# ai_avr_synth.net
KiCad netlist of a schematic drawn in EAGLE
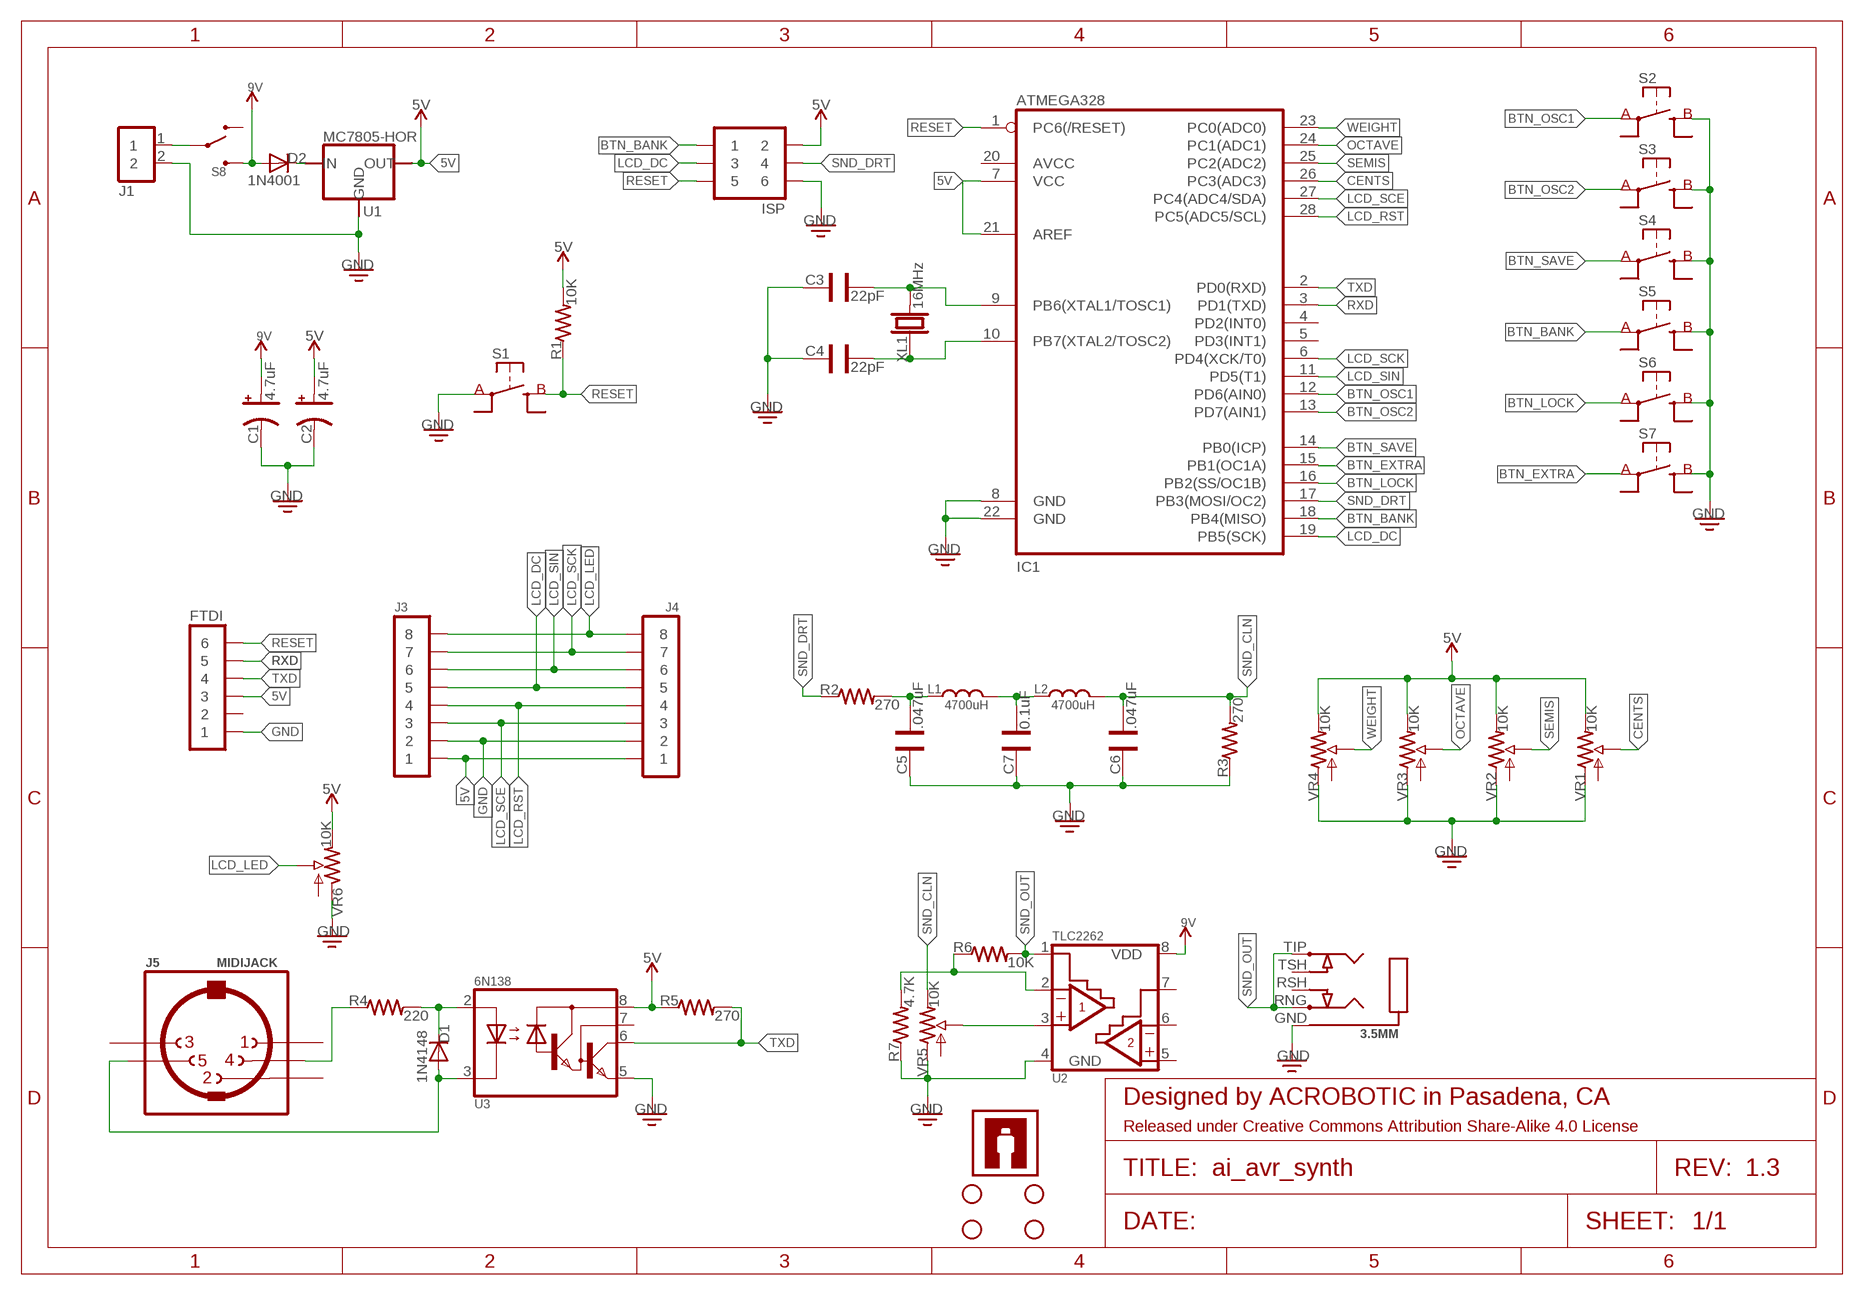
[diagram p0: schematic, sheet 1]

(export (version "E")
  (design (tool "Eeschema 10.0.6"))
  (components
    (comp (ref "3.5MM")
      (value "STEREOJACKSJ1-351XNG")
      (footprint "eagle-import:SJ1-351XNG")
      (libsource (lib "eagle-import") (part "STEREOJACKSJ1-351XNG"))
    )
    (comp (ref "C1")
      (value "4.7uF")
      (footprint "eagle-import:CAP-POL-025X50")
      (libsource (lib "eagle-import") (part "CAP-POL025X50"))
    )
    (comp (ref "C2")
      (value "4.7uF")
      (footprint "eagle-import:CAP-POL-025X50")
      (libsource (lib "eagle-import") (part "CAP-POL025X50"))
    )
    (comp (ref "C3")
      (value "22pF")
      (footprint "eagle-import:CAP-025X050")
      (libsource (lib "eagle-import") (part "CAP025X050"))
    )
    (comp (ref "C4")
      (value "22pF")
      (footprint "eagle-import:CAP-025X050")
      (libsource (lib "eagle-import") (part "CAP025X050"))
    )
    (comp (ref "C5")
      (value ".047uF")
      (footprint "eagle-import:CAP-025X050")
      (libsource (lib "eagle-import") (part "CAP025X050"))
    )
    (comp (ref "C6")
      (value ".047uF")
      (footprint "eagle-import:CAP-025X050")
      (libsource (lib "eagle-import") (part "CAP025X050"))
    )
    (comp (ref "C7")
      (value "0.1uF")
      (footprint "eagle-import:CAP-025X050")
      (libsource (lib "eagle-import") (part "CAP025X050"))
    )
    (comp (ref "D1")
      (value "1N4148")
      (footprint "eagle-import:TH-1N914")
      (libsource (lib "eagle-import") (part "DIODETH-1N914"))
    )
    (comp (ref "D2")
      (value "1N4001")
      (footprint "eagle-import:TH-1N914")
      (libsource (lib "eagle-import") (part "DIODETH-1N914"))
    )
    (comp (ref "FRAME1")
      (value "FRAME-LETTER")
      (footprint "eagle-import:CREATIVE-COMMONS")
      (fields (field (name "REV") "1.3"))
      (libsource (lib "eagle-import") (part "FRAME-LETTER"))
    )
    (comp (ref "FTDI")
      (value "1X06")
      (footprint "eagle-import:1X06")
      (libsource (lib "eagle-import") (part "1X06"))
    )
    (comp (ref "IC1")
      (value "ATMEGA328P-PDIP")
      (footprint "eagle-import:DIL28")
      (libsource (lib "eagle-import") (part "ATMEGA328P-PDIP"))
    )
    (comp (ref "ISP")
      (value "2X03")
      (footprint "eagle-import:2X03")
      (libsource (lib "eagle-import") (part "2X03"))
    )
    (comp (ref "J1")
      (value "1X02ST")
      (footprint "eagle-import:1X02-ST")
      (libsource (lib "eagle-import") (part "1X02ST"))
    )
    (comp (ref "J3")
      (value "1X08")
      (footprint "eagle-import:1X08")
      (libsource (lib "eagle-import") (part "1X08"))
    )
    (comp (ref "J4")
      (value "1X08")
      (footprint "eagle-import:1X08")
      (libsource (lib "eagle-import") (part "1X08"))
    )
    (comp (ref "J5")
      (value "MIDIJACK")
      (footprint "eagle-import:CP-2350")
      (libsource (lib "eagle-import") (part "MIDIJACK"))
    )
    (comp (ref "L1")
      (value "4700uH")
      (footprint "eagle-import:RLB0912")
      (libsource (lib "eagle-import") (part "INDRLB0912"))
    )
    (comp (ref "L2")
      (value "4700uH")
      (footprint "eagle-import:RLB0912")
      (libsource (lib "eagle-import") (part "INDRLB0912"))
    )
    (comp (ref "R1")
      (value "10K")
      (footprint "eagle-import:RES-AXIAL-0.4")
      (libsource (lib "eagle-import") (part "RESAXIAL-0.4"))
    )
    (comp (ref "R2")
      (value "270")
      (footprint "eagle-import:RES-AXIAL-0.4")
      (libsource (lib "eagle-import") (part "RESAXIAL-0.4"))
    )
    (comp (ref "R3")
      (value "270")
      (footprint "eagle-import:RES-AXIAL-0.4")
      (libsource (lib "eagle-import") (part "RESAXIAL-0.4"))
    )
    (comp (ref "R4")
      (value "220")
      (footprint "eagle-import:RES-AXIAL-0.4")
      (libsource (lib "eagle-import") (part "RESAXIAL-0.4"))
    )
    (comp (ref "R5")
      (value "270")
      (footprint "eagle-import:RES-AXIAL-0.4")
      (libsource (lib "eagle-import") (part "RESAXIAL-0.4"))
    )
    (comp (ref "R6")
      (value "10K")
      (footprint "eagle-import:RES-AXIAL-0.4")
      (libsource (lib "eagle-import") (part "RESAXIAL-0.4"))
    )
    (comp (ref "R7")
      (value "4.7K")
      (footprint "eagle-import:RES-AXIAL-0.4")
      (libsource (lib "eagle-import") (part "RESAXIAL-0.4"))
    )
    (comp (ref "S1")
      (value "SW-SPSTTH06X06")
      (footprint "eagle-import:SW-SPST-TH06X06")
      (libsource (lib "eagle-import") (part "SW-SPSTTH06X06"))
    )
    (comp (ref "S2")
      (value "SW-SPSTTH06X06")
      (footprint "eagle-import:SW-SPST-TH06X06")
      (libsource (lib "eagle-import") (part "SW-SPSTTH06X06"))
    )
    (comp (ref "S3")
      (value "SW-SPSTTH06X06")
      (footprint "eagle-import:SW-SPST-TH06X06")
      (libsource (lib "eagle-import") (part "SW-SPSTTH06X06"))
    )
    (comp (ref "S4")
      (value "SW-SPSTTH06X06")
      (footprint "eagle-import:SW-SPST-TH06X06")
      (libsource (lib "eagle-import") (part "SW-SPSTTH06X06"))
    )
    (comp (ref "S5")
      (value "SW-SPSTTH06X06")
      (footprint "eagle-import:SW-SPST-TH06X06")
      (libsource (lib "eagle-import") (part "SW-SPSTTH06X06"))
    )
    (comp (ref "S6")
      (value "SW-SPSTTH06X06")
      (footprint "eagle-import:SW-SPST-TH06X06")
      (libsource (lib "eagle-import") (part "SW-SPSTTH06X06"))
    )
    (comp (ref "S7")
      (value "SW-SPSTTH06X06")
      (footprint "eagle-import:SW-SPST-TH06X06")
      (libsource (lib "eagle-import") (part "SW-SPSTTH06X06"))
    )
    (comp (ref "S8")
      (value "SW-SPDTTH")
      (footprint "eagle-import:SW-SPDT-TH")
      (libsource (lib "eagle-import") (part "SW-SPDTTH"))
    )
    (comp (ref "STANDOFF5")
      (value "STAND-OFF4")
      (footprint "eagle-import:STAND-OFF-4")
      (libsource (lib "eagle-import") (part "STAND-OFF4"))
    )
    (comp (ref "STANDOFF6")
      (value "STAND-OFF4")
      (footprint "eagle-import:STAND-OFF-4")
      (libsource (lib "eagle-import") (part "STAND-OFF4"))
    )
    (comp (ref "STANDOFF7")
      (value "STAND-OFF4")
      (footprint "eagle-import:STAND-OFF-4")
      (libsource (lib "eagle-import") (part "STAND-OFF4"))
    )
    (comp (ref "STANDOFF8")
      (value "STAND-OFF4")
      (footprint "eagle-import:STAND-OFF-4")
      (libsource (lib "eagle-import") (part "STAND-OFF4"))
    )
    (comp (ref "U$5")
      (value "AI-LOGOXS")
      (footprint "eagle-import:AI-LOGO-XS")
      (libsource (lib "eagle-import") (part "AI-LOGOXS"))
    )
    (comp (ref "U1")
      (value "MC7805-HOR")
      (footprint "eagle-import:TO220")
      (libsource (lib "eagle-import") (part "MC7805-HOR"))
    )
    (comp (ref "U2")
      (value "TLC2262")
      (footprint "eagle-import:DIL08")
      (libsource (lib "eagle-import") (part "TLC2262"))
    )
    (comp (ref "U3")
      (value "6N138")
      (footprint "eagle-import:DIL08")
      (libsource (lib "eagle-import") (part "6N138"))
    )
    (comp (ref "VR1")
      (value "10K")
      (footprint "eagle-import:POT-09X09")
      (libsource (lib "eagle-import") (part "POT09X09"))
    )
    (comp (ref "VR2")
      (value "10K")
      (footprint "eagle-import:POT-09X09")
      (libsource (lib "eagle-import") (part "POT09X09"))
    )
    (comp (ref "VR3")
      (value "10K")
      (footprint "eagle-import:POT-09X09")
      (libsource (lib "eagle-import") (part "POT09X09"))
    )
    (comp (ref "VR4")
      (value "10K")
      (footprint "eagle-import:POT-09X09")
      (libsource (lib "eagle-import") (part "POT09X09"))
    )
    (comp (ref "VR5")
      (value "10K")
      (footprint "eagle-import:POT-09X09")
      (libsource (lib "eagle-import") (part "POT09X09"))
    )
    (comp (ref "VR6")
      (value "10K")
      (footprint "eagle-import:POT-05X05")
      (libsource (lib "eagle-import") (part "POT05X05"))
    )
    (comp (ref "XL1")
      (value "16MHz")
      (footprint "eagle-import:HC49S")
      (libsource (lib "eagle-import") (part "CRYSTALHC49S"))
    )
  )
  (nets
    (net (code "1") (name "5V") (class "Default")
      (node (ref "C2") (pin "A") (pinfunction "A_A") (pintype "passive"))
      (node (ref "FTDI") (pin "3") (pinfunction "3_3") (pintype "bidirectional"))
      (node (ref "IC1") (pin "21") (pinfunction "AREF_21") (pintype "bidirectional"))
      (node (ref "IC1") (pin "7") (pinfunction "VCC_7") (pintype "bidirectional"))
      (node (ref "ISP") (pin "2") (pinfunction "2_2") (pintype "bidirectional"))
      (node (ref "J3") (pin "1") (pinfunction "1_1") (pintype "bidirectional"))
      (node (ref "J4") (pin "1") (pinfunction "1_1") (pintype "bidirectional"))
      (node (ref "R1") (pin "P$2") (pinfunction "2_P$2") (pintype "passive"))
      (node (ref "R5") (pin "P$1") (pinfunction "1_P$1") (pintype "passive"))
      (node (ref "U1") (pin "OUT") (pinfunction "OUT_OUT") (pintype "power_in"))
      (node (ref "U3") (pin "8") (pinfunction "VCC_8") (pintype "passive"))
      (node (ref "VR1") (pin "P$1") (pinfunction "E_P$1") (pintype "passive"))
      (node (ref "VR2") (pin "P$1") (pinfunction "E_P$1") (pintype "passive"))
      (node (ref "VR3") (pin "P$1") (pinfunction "E_P$1") (pintype "passive"))
      (node (ref "VR4") (pin "P$1") (pinfunction "E_P$1") (pintype "passive"))
      (node (ref "VR6") (pin "1") (pinfunction "E_1") (pintype "passive"))
    )
    (net (code "2") (name "9V") (class "Default")
      (node (ref "C1") (pin "A") (pinfunction "A_A") (pintype "passive"))
      (node (ref "D2") (pin "A") (pinfunction "A_A") (pintype "passive"))
      (node (ref "S8") (pin "3") (pinfunction "L2_3") (pintype "passive"))
      (node (ref "U2") (pin "8") (pinfunction "VDD_8") (pintype "power_in"))
    )
    (net (code "3") (name "BTN_BANK") (class "Default")
      (node (ref "IC1") (pin "18") (pinfunction "PB4(MISO)_18") (pintype "bidirectional"))
      (node (ref "ISP") (pin "1") (pinfunction "1_1") (pintype "bidirectional"))
      (node (ref "S5") (pin "A@1") (pinfunction "A_A@1") (pintype "passive"))
    )
    (net (code "4") (name "BTN_EXTRA") (class "Default")
      (node (ref "IC1") (pin "15") (pinfunction "PB1(OC1A)_15") (pintype "bidirectional"))
      (node (ref "S7") (pin "A@1") (pinfunction "A_A@1") (pintype "passive"))
    )
    (net (code "5") (name "BTN_LOCK") (class "Default")
      (node (ref "IC1") (pin "16") (pinfunction "PB2(SS/OC1B)_16") (pintype "bidirectional"))
      (node (ref "S6") (pin "A@1") (pinfunction "A_A@1") (pintype "passive"))
    )
    (net (code "6") (name "BTN_OSC1") (class "Default")
      (node (ref "IC1") (pin "12") (pinfunction "PD6(AIN0)_12") (pintype "bidirectional"))
      (node (ref "S2") (pin "A@1") (pinfunction "A_A@1") (pintype "passive"))
    )
    (net (code "7") (name "BTN_OSC2") (class "Default")
      (node (ref "IC1") (pin "13") (pinfunction "PD7(AIN1)_13") (pintype "bidirectional"))
      (node (ref "S3") (pin "A@1") (pinfunction "A_A@1") (pintype "passive"))
    )
    (net (code "8") (name "BTN_SAVE") (class "Default")
      (node (ref "IC1") (pin "14") (pinfunction "PB0(ICP)_14") (pintype "bidirectional"))
      (node (ref "S4") (pin "A@1") (pinfunction "A_A@1") (pintype "passive"))
    )
    (net (code "9") (name "CENTS") (class "Default")
      (node (ref "IC1") (pin "26") (pinfunction "PC3(ADC3)_26") (pintype "bidirectional"))
      (node (ref "VR1") (pin "P$2") (pinfunction "S_P$2") (pintype "passive"))
    )
    (net (code "10") (name "GND") (class "Default")
      (node (ref "3.5MM") (pin "GND") (pinfunction "GND_GND") (pintype "passive"))
      (node (ref "C1") (pin "C") (pinfunction "C_C") (pintype "passive"))
      (node (ref "C2") (pin "C") (pinfunction "C_C") (pintype "passive"))
      (node (ref "C3") (pin "2") (pinfunction "2_2") (pintype "passive"))
      (node (ref "C4") (pin "2") (pinfunction "2_2") (pintype "passive"))
      (node (ref "C5") (pin "2") (pinfunction "2_2") (pintype "passive"))
      (node (ref "C6") (pin "2") (pinfunction "2_2") (pintype "passive"))
      (node (ref "C7") (pin "2") (pinfunction "2_2") (pintype "passive"))
      (node (ref "FTDI") (pin "1") (pinfunction "1_1") (pintype "bidirectional"))
      (node (ref "IC1") (pin "22") (pinfunction "GND_22") (pintype "bidirectional"))
      (node (ref "IC1") (pin "8") (pinfunction "GND_8") (pintype "bidirectional"))
      (node (ref "ISP") (pin "6") (pinfunction "6_6") (pintype "bidirectional"))
      (node (ref "J1") (pin "2") (pinfunction "2_2") (pintype "bidirectional"))
      (node (ref "J3") (pin "2") (pinfunction "2_2") (pintype "bidirectional"))
      (node (ref "J4") (pin "2") (pinfunction "2_2") (pintype "bidirectional"))
      (node (ref "R3") (pin "P$1") (pinfunction "1_P$1") (pintype "passive"))
      (node (ref "R7") (pin "P$1") (pinfunction "1_P$1") (pintype "passive"))
      (node (ref "S1") (pin "A@1") (pinfunction "A_A@1") (pintype "passive"))
      (node (ref "S2") (pin "B@1") (pinfunction "B_B@1") (pintype "passive"))
      (node (ref "S3") (pin "B@1") (pinfunction "B_B@1") (pintype "passive"))
      (node (ref "S4") (pin "B@1") (pinfunction "B_B@1") (pintype "passive"))
      (node (ref "S5") (pin "B@1") (pinfunction "B_B@1") (pintype "passive"))
      (node (ref "S6") (pin "B@1") (pinfunction "B_B@1") (pintype "passive"))
      (node (ref "S7") (pin "B@1") (pinfunction "B_B@1") (pintype "passive"))
      (node (ref "U1") (pin "GND") (pinfunction "GND_GND") (pintype "input"))
      (node (ref "U2") (pin "4") (pinfunction "GND_4") (pintype "power_in"))
      (node (ref "U3") (pin "5") (pinfunction "GND_5") (pintype "passive"))
      (node (ref "VR1") (pin "P$3") (pinfunction "A_P$3") (pintype "passive"))
      (node (ref "VR2") (pin "P$3") (pinfunction "A_P$3") (pintype "passive"))
      (node (ref "VR3") (pin "P$3") (pinfunction "A_P$3") (pintype "passive"))
      (node (ref "VR4") (pin "P$3") (pinfunction "A_P$3") (pintype "passive"))
      (node (ref "VR5") (pin "P$3") (pinfunction "A_P$3") (pintype "passive"))
      (node (ref "VR6") (pin "3") (pinfunction "A_3") (pintype "passive"))
    )
    (net (code "11") (name "LCD_DC") (class "Default")
      (node (ref "IC1") (pin "19") (pinfunction "PB5(SCK)_19") (pintype "bidirectional"))
      (node (ref "ISP") (pin "3") (pinfunction "3_3") (pintype "bidirectional"))
      (node (ref "J3") (pin "5") (pinfunction "5_5") (pintype "bidirectional"))
      (node (ref "J4") (pin "5") (pinfunction "5_5") (pintype "bidirectional"))
    )
    (net (code "12") (name "LCD_LED") (class "Default")
      (node (ref "J3") (pin "8") (pinfunction "8_8") (pintype "bidirectional"))
      (node (ref "J4") (pin "8") (pinfunction "8_8") (pintype "bidirectional"))
      (node (ref "VR6") (pin "2") (pinfunction "S_2") (pintype "passive"))
    )
    (net (code "13") (name "LCD_RST") (class "Default")
      (node (ref "IC1") (pin "28") (pinfunction "PC5(ADC5/SCL)_28") (pintype "bidirectional"))
      (node (ref "J3") (pin "4") (pinfunction "4_4") (pintype "bidirectional"))
      (node (ref "J4") (pin "4") (pinfunction "4_4") (pintype "bidirectional"))
    )
    (net (code "14") (name "LCD_SCE") (class "Default")
      (node (ref "IC1") (pin "27") (pinfunction "PC4(ADC4/SDA)_27") (pintype "bidirectional"))
      (node (ref "J3") (pin "3") (pinfunction "3_3") (pintype "bidirectional"))
      (node (ref "J4") (pin "3") (pinfunction "3_3") (pintype "bidirectional"))
    )
    (net (code "15") (name "LCD_SCK") (class "Default")
      (node (ref "IC1") (pin "6") (pinfunction "PD4(XCK/T0)_6") (pintype "bidirectional"))
      (node (ref "J3") (pin "7") (pinfunction "7_7") (pintype "bidirectional"))
      (node (ref "J4") (pin "7") (pinfunction "7_7") (pintype "bidirectional"))
    )
    (net (code "16") (name "LCD_SIN") (class "Default")
      (node (ref "IC1") (pin "11") (pinfunction "PD5(T1)_11") (pintype "bidirectional"))
      (node (ref "J3") (pin "6") (pinfunction "6_6") (pintype "bidirectional"))
      (node (ref "J4") (pin "6") (pinfunction "6_6") (pintype "bidirectional"))
    )
    (net (code "17") (name "Net-(C7-Pad1)") (class "Default")
      (node (ref "C7") (pin "1") (pinfunction "1_1") (pintype "passive"))
      (node (ref "L1") (pin "1") (pinfunction "1_1") (pintype "passive"))
      (node (ref "L2") (pin "2") (pinfunction "2_2") (pintype "passive"))
    )
    (net (code "18") (name "Net-(D2-PadC)") (class "Default")
      (node (ref "D2") (pin "C") (pinfunction "C_C") (pintype "passive"))
      (node (ref "U1") (pin "IN") (pinfunction "IN_IN") (pintype "power_in"))
    )
    (net (code "19") (name "Net-(IC1-PB6(XTAL1{slash}TOSC1))") (class "Default")
      (node (ref "C3") (pin "1") (pinfunction "1_1") (pintype "passive"))
      (node (ref "IC1") (pin "9") (pinfunction "PB6(XTAL1/TOSC1)_9") (pintype "bidirectional"))
      (node (ref "XL1") (pin "2") (pinfunction "2_2") (pintype "passive"))
    )
    (net (code "20") (name "Net-(IC1-PB7(XTAL2{slash}TOSC2))") (class "Default")
      (node (ref "C4") (pin "1") (pinfunction "1_1") (pintype "passive"))
      (node (ref "IC1") (pin "10") (pinfunction "PB7(XTAL2/TOSC2)_10") (pintype "bidirectional"))
      (node (ref "XL1") (pin "1") (pinfunction "1_1") (pintype "passive"))
    )
    (net (code "21") (name "Net-(R2-2)") (class "Default")
      (node (ref "C5") (pin "1") (pinfunction "1_1") (pintype "passive"))
      (node (ref "L1") (pin "2") (pinfunction "2_2") (pintype "passive"))
      (node (ref "R2") (pin "P$2") (pinfunction "2_P$2") (pintype "passive"))
    )
    (net (code "22") (name "Net-(R4-1)") (class "Default")
      (node (ref "J5") (pin "4") (pinfunction "4_4") (pintype "passive"))
      (node (ref "R4") (pin "P$1") (pinfunction "1_P$1") (pintype "passive"))
    )
    (net (code "23") (name "Net-(R4-2)") (class "Default")
      (node (ref "D1") (pin "C") (pinfunction "C_C") (pintype "passive"))
      (node (ref "R4") (pin "P$2") (pinfunction "2_P$2") (pintype "passive"))
      (node (ref "U3") (pin "2") (pinfunction "A_2") (pintype "passive"))
    )
    (net (code "24") (name "Net-(R6-1)") (class "Default")
      (node (ref "R6") (pin "P$1") (pinfunction "1_P$1") (pintype "passive"))
      (node (ref "R7") (pin "P$2") (pinfunction "2_P$2") (pintype "passive"))
      (node (ref "U2") (pin "2") (pinfunction "1IN-_2") (pintype "input"))
    )
    (net (code "25") (name "Net-(S8-COM)") (class "Default")
      (node (ref "J1") (pin "1") (pinfunction "1_1") (pintype "bidirectional"))
      (node (ref "S8") (pin "2") (pinfunction "COM_2") (pintype "passive"))
    )
    (net (code "26") (name "Net-(U2-1IN+)") (class "Default")
      (node (ref "U2") (pin "3") (pinfunction "1IN+_3") (pintype "input"))
      (node (ref "VR5") (pin "P$2") (pinfunction "S_P$2") (pintype "passive"))
    )
    (net (code "27") (name "Net-(U3-C)") (class "Default")
      (node (ref "D1") (pin "A") (pinfunction "A_A") (pintype "passive"))
      (node (ref "J5") (pin "5") (pinfunction "5_5") (pintype "passive"))
      (node (ref "U3") (pin "3") (pinfunction "C_3") (pintype "passive"))
    )
    (net (code "28") (name "OCTAVE") (class "Default")
      (node (ref "IC1") (pin "24") (pinfunction "PC1(ADC1)_24") (pintype "bidirectional"))
      (node (ref "VR3") (pin "P$2") (pinfunction "S_P$2") (pintype "passive"))
    )
    (net (code "29") (name "RESET") (class "Default")
      (node (ref "FTDI") (pin "6") (pinfunction "6_6") (pintype "bidirectional"))
      (node (ref "IC1") (pin "1") (pinfunction "PC6(/RESET)_1") (pintype "bidirectional"))
      (node (ref "ISP") (pin "5") (pinfunction "5_5") (pintype "bidirectional"))
      (node (ref "R1") (pin "P$1") (pinfunction "1_P$1") (pintype "passive"))
      (node (ref "S1") (pin "B@1") (pinfunction "B_B@1") (pintype "passive"))
    )
    (net (code "30") (name "RXD") (class "Default")
      (node (ref "FTDI") (pin "5") (pinfunction "5_5") (pintype "bidirectional"))
      (node (ref "IC1") (pin "3") (pinfunction "PD1(TXD)_3") (pintype "bidirectional"))
    )
    (net (code "31") (name "SEMIS") (class "Default")
      (node (ref "IC1") (pin "25") (pinfunction "PC2(ADC2)_25") (pintype "bidirectional"))
      (node (ref "VR2") (pin "P$2") (pinfunction "S_P$2") (pintype "passive"))
    )
    (net (code "32") (name "SND_CLN") (class "Default")
      (node (ref "C6") (pin "1") (pinfunction "1_1") (pintype "passive"))
      (node (ref "L2") (pin "1") (pinfunction "1_1") (pintype "passive"))
      (node (ref "R3") (pin "P$2") (pinfunction "2_P$2") (pintype "passive"))
      (node (ref "VR5") (pin "P$1") (pinfunction "E_P$1") (pintype "passive"))
    )
    (net (code "33") (name "SND_DRT") (class "Default")
      (node (ref "IC1") (pin "17") (pinfunction "PB3(MOSI/OC2)_17") (pintype "bidirectional"))
      (node (ref "ISP") (pin "4") (pinfunction "4_4") (pintype "bidirectional"))
      (node (ref "R2") (pin "P$1") (pinfunction "1_P$1") (pintype "passive"))
    )
    (net (code "34") (name "SND_OUT") (class "Default")
      (node (ref "3.5MM") (pin "RNG") (pinfunction "RNG_RNG") (pintype "passive"))
      (node (ref "3.5MM") (pin "TIP") (pinfunction "TIP_TIP") (pintype "passive"))
      (node (ref "R6") (pin "P$2") (pinfunction "2_P$2") (pintype "passive"))
      (node (ref "U2") (pin "1") (pinfunction "1OUT_1") (pintype "output"))
    )
    (net (code "35") (name "TXD") (class "Default")
      (node (ref "FTDI") (pin "4") (pinfunction "4_4") (pintype "bidirectional"))
      (node (ref "IC1") (pin "2") (pinfunction "PD0(RXD)_2") (pintype "bidirectional"))
      (node (ref "R5") (pin "P$2") (pinfunction "2_P$2") (pintype "passive"))
      (node (ref "U3") (pin "6") (pinfunction "VO_6") (pintype "passive"))
    )
    (net (code "36") (name "WEIGHT") (class "Default")
      (node (ref "IC1") (pin "23") (pinfunction "PC0(ADC0)_23") (pintype "bidirectional"))
      (node (ref "VR4") (pin "P$2") (pinfunction "S_P$2") (pintype "passive"))
    )
    (net (code "37") (name "unconnected-(3.5MM-PadRSH)") (class "Default")
      (node (ref "3.5MM") (pin "RSH") (pinfunction "RSH_RSH") (pintype "passive"))
    )
    (net (code "38") (name "unconnected-(3.5MM-PadTSH)") (class "Default")
      (node (ref "3.5MM") (pin "TSH") (pinfunction "TSH_TSH") (pintype "passive"))
    )
    (net (code "39") (name "unconnected-(FTDI-Pad2)") (class "Default")
      (node (ref "FTDI") (pin "2") (pinfunction "2_2") (pintype "bidirectional"))
    )
    (net (code "40") (name "unconnected-(IC1-AVCC-Pad20)") (class "Default")
      (node (ref "IC1") (pin "20") (pinfunction "AVCC_20") (pintype "bidirectional"))
    )
    (net (code "41") (name "unconnected-(IC1-PD2(INT0)-Pad4)") (class "Default")
      (node (ref "IC1") (pin "4") (pinfunction "PD2(INT0)_4") (pintype "bidirectional"))
    )
    (net (code "42") (name "unconnected-(IC1-PD3(INT1)-Pad5)") (class "Default")
      (node (ref "IC1") (pin "5") (pinfunction "PD3(INT1)_5") (pintype "bidirectional"))
    )
    (net (code "43") (name "unconnected-(J5-Pad1)") (class "Default")
      (node (ref "J5") (pin "1") (pinfunction "1_1") (pintype "passive"))
    )
    (net (code "44") (name "unconnected-(J5-Pad2)") (class "Default")
      (node (ref "J5") (pin "2") (pinfunction "2_2") (pintype "passive"))
    )
    (net (code "45") (name "unconnected-(J5-Pad3)") (class "Default")
      (node (ref "J5") (pin "3") (pinfunction "3_3") (pintype "passive"))
    )
    (net (code "46") (name "unconnected-(S8-L1-Pad1)") (class "Default")
      (node (ref "S8") (pin "1") (pinfunction "L1_1") (pintype "passive"))
    )
    (net (code "47") (name "unconnected-(U2-2IN+-Pad5)") (class "Default")
      (node (ref "U2") (pin "5") (pinfunction "2IN+_5") (pintype "input"))
    )
    (net (code "48") (name "unconnected-(U2-2IN--Pad6)") (class "Default")
      (node (ref "U2") (pin "6") (pinfunction "2IN-_6") (pintype "input"))
    )
    (net (code "49") (name "unconnected-(U2-2OUT-Pad7)") (class "Default")
      (node (ref "U2") (pin "7") (pinfunction "2OUT_7") (pintype "output"))
    )
    (net (code "50") (name "unconnected-(U3-VB-Pad7)") (class "Default")
      (node (ref "U3") (pin "7") (pinfunction "VB_7") (pintype "passive"))
    )
  )
)
